# Pg5-Power_supply_2.net
KiCad netlist of a schematic drawn in Altium Designer
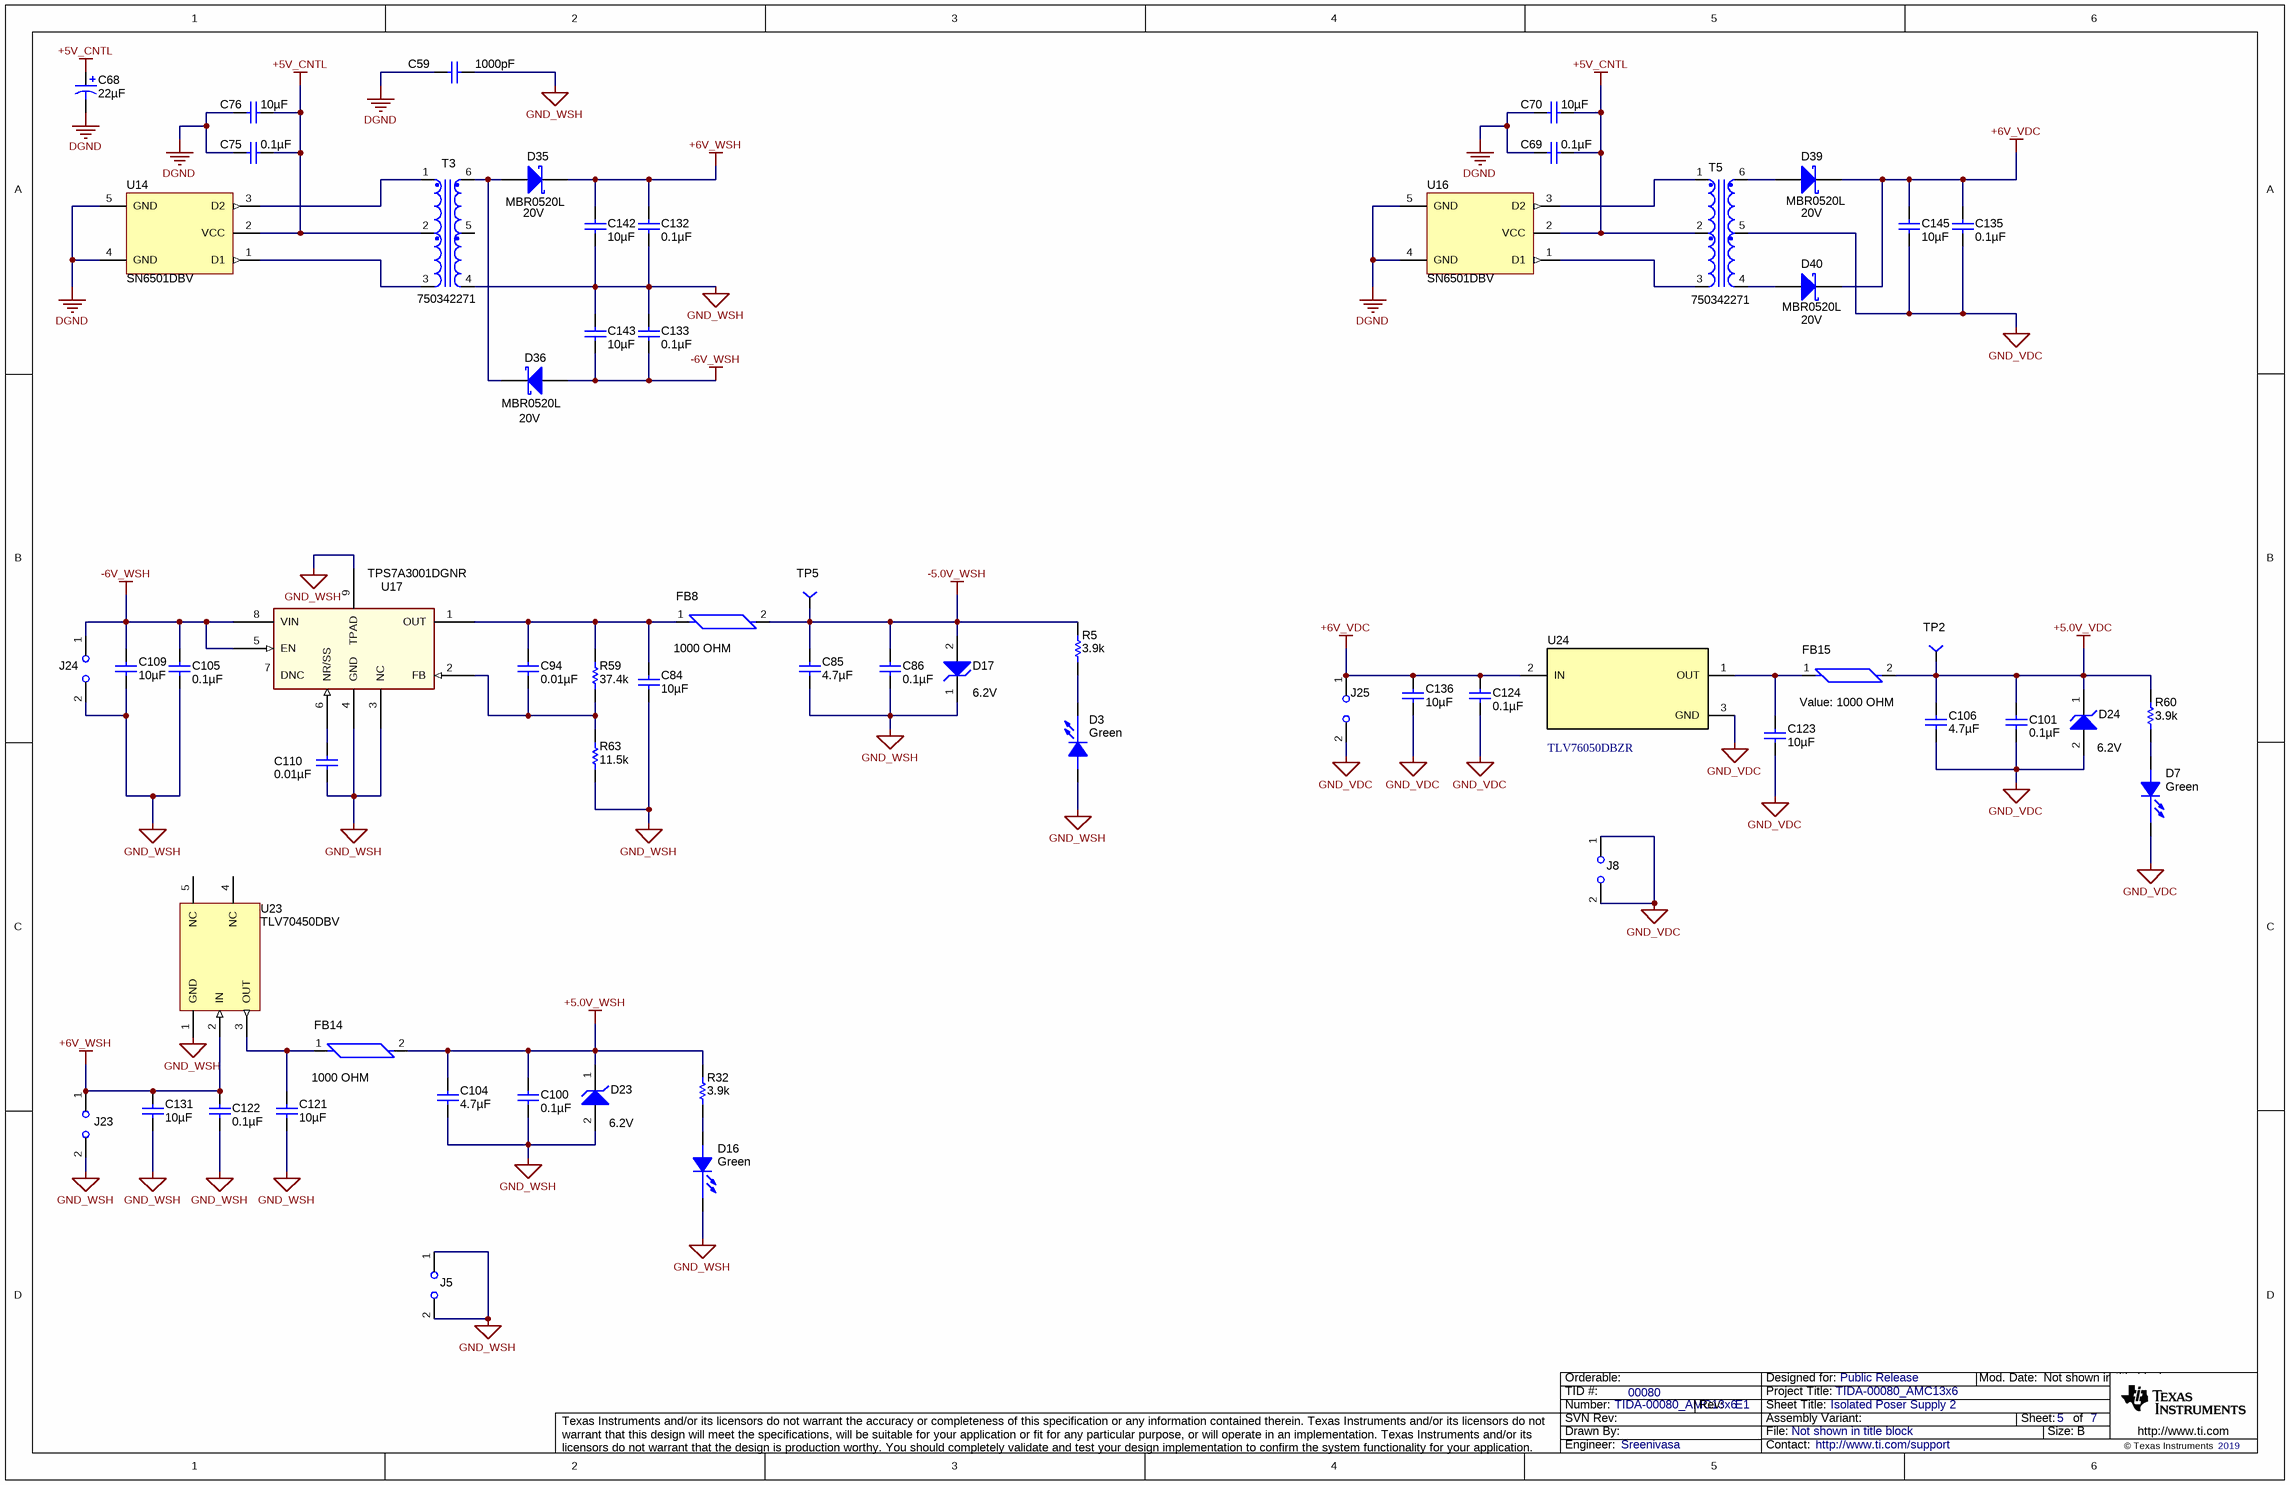
[diagram p0: Pg5-Power supply 2.SchDoc]

(export (version "E")
  (design (tool "Eeschema 10.0.6"))
  (components
    (comp (ref "C59")
      (value "1000pF")
      (footprint "CAP_200mil")
      (description "CAP CER 1000PF 1KV 10% RADIAL")
      (fields
        (field (name "PARTNUMBER") "S102K29Y5PN63J5R")
        (field (name "MANUFACTURER") "Vishay BC Components")
        (field (name "PUBLISHER") "Texas Instruments")
      )
      (libsource (lib "TI-INDIA-ALTIUM") (part "202R18W102KV4E"))
    )
    (comp (ref "C68")
      (value "UUD1E220MCL1GS")
      (footprint "ISE_MCS_SDM_E1_20MAY:SM_RADIAL_5MM")
      (description "CAP, AL, 22uF, 25V, +/-20%, 0.76 ohm, SMD")
      (fields
        (field (name "VALUEDISPLAYED") "22µF")
        (field (name "MANUFACTURER") "Nichicon")
        (field (name "PUBLISHER") "Texas Instruments")
      )
      (libsource (lib "Capacitor_Aluminum") (part "UUD1E220MCL1GS"))
    )
    (comp (ref "C69")
      (value "~")
      (footprint "ISE_MCS_SDM_E1_20MAY:0603")
      (description "CAP, CERM, 0.1uF, 50V, +/-10%, X7R, 0603")
      (fields
        (field (name "PARTNUMBER") "C0603C104K5RACTU")
        (field (name "VALUEDISPLAYED") "0.1µF")
        (field (name "MANUFACTURER") "Kemet")
        (field (name "PUBLISHER") "Texas Instruments")
      )
      (libsource (lib "Capacitor_Ceramic") (part "C0603C104K5RACTU"))
    )
    (comp (ref "C70")
      (value "~")
      (footprint "ISE_MCS_SDM_E1_20MAY:1210")
      (description "CAP, CERM, 10uF, 35V, +/-20%, X7R, 1210")
      (fields
        (field (name "PARTNUMBER") "GMK325AB7106MM-T")
        (field (name "VALUEDISPLAYED") "10µF")
        (field (name "MANUFACTURER") "Taiyo Yuden")
        (field (name "PUBLISHER") "Texas Instruments")
      )
      (libsource (lib "Capacitor_Ceramic") (part "GMK325AB7106MM-T"))
    )
    (comp (ref "C75")
      (value "~")
      (footprint "ISE_MCS_SDM_E1_20MAY:0603")
      (description "CAP, CERM, 0.1uF, 50V, +/-10%, X7R, 0603")
      (fields
        (field (name "PARTNUMBER") "C0603C104K5RACTU")
        (field (name "VALUEDISPLAYED") "0.1µF")
        (field (name "MANUFACTURER") "Kemet")
        (field (name "PUBLISHER") "Texas Instruments")
      )
      (libsource (lib "Capacitor_Ceramic") (part "C0603C104K5RACTU"))
    )
    (comp (ref "C76")
      (value "~")
      (footprint "ISE_MCS_SDM_E1_20MAY:1210")
      (description "CAP, CERM, 10uF, 35V, +/-20%, X7R, 1210")
      (fields
        (field (name "PARTNUMBER") "GMK325AB7106MM-T")
        (field (name "VALUEDISPLAYED") "10µF")
        (field (name "MANUFACTURER") "Taiyo Yuden")
        (field (name "PUBLISHER") "Texas Instruments")
      )
      (libsource (lib "Capacitor_Ceramic") (part "GMK325AB7106MM-T"))
    )
    (comp (ref "C84")
      (value "~")
      (footprint "ISE_MCS_SDM_E1_20MAY:1210")
      (description "CAP, CERM, 10uF, 35V, +/-20%, X7R, 1210")
      (fields
        (field (name "PARTNUMBER") "GMK325AB7106MM-T")
        (field (name "VALUEDISPLAYED") "10µF")
        (field (name "MANUFACTURER") "Taiyo Yuden")
        (field (name "PUBLISHER") "Texas Instruments")
      )
      (libsource (lib "Capacitor_Ceramic") (part "GMK325AB7106MM-T"))
    )
    (comp (ref "C85")
      (value "~")
      (footprint "ISE_MCS_SDM_E1_20MAY:0805_HV")
      (description "CAP, CERM, 4.7uF, 50V, +/-10%, X5R, 0805")
      (fields
        (field (name "PARTNUMBER") "C2012X5R1H475K125AB")
        (field (name "VALUEDISPLAYED") "4.7µF")
        (field (name "MANUFACTURER") "TDK")
        (field (name "PUBLISHER") "Texas Instruments")
      )
      (libsource (lib "Capacitor_Ceramic") (part "C2012X5R1H475K125AB"))
    )
    (comp (ref "C86")
      (value "~")
      (footprint "ISE_MCS_SDM_E1_20MAY:0603")
      (description "CAP, CERM, 0.1uF, 50V, +/-10%, X7R, 0603")
      (fields
        (field (name "PARTNUMBER") "C0603C104K5RACTU")
        (field (name "VALUEDISPLAYED") "0.1µF")
        (field (name "MANUFACTURER") "Kemet")
        (field (name "PUBLISHER") "Texas Instruments")
      )
      (libsource (lib "Capacitor_Ceramic") (part "C0603C104K5RACTU"))
    )
    (comp (ref "C94")
      (value "~")
      (footprint "ISE_MCS_SDM_E1_20MAY:0603")
      (description "CAP, CERM, 0.01uF, 100V, +/-5%, X7R, 0603")
      (fields
        (field (name "PARTNUMBER") "06031C103J4Z4A")
        (field (name "VALUEDISPLAYED") "0.01µF")
        (field (name "MANUFACTURER") "AVX")
        (field (name "PUBLISHER") "Texas Instruments")
      )
      (libsource (lib "Capacitor_Ceramic") (part "06031C103J4Z4A"))
    )
    (comp (ref "C100")
      (value "~")
      (footprint "ISE_MCS_SDM_E1_20MAY:0603")
      (description "CAP, CERM, 0.1uF, 50V, +/-10%, X7R, 0603")
      (fields
        (field (name "PARTNUMBER") "C0603C104K5RACTU")
        (field (name "VALUEDISPLAYED") "0.1µF")
        (field (name "MANUFACTURER") "Kemet")
        (field (name "PUBLISHER") "Texas Instruments")
      )
      (libsource (lib "Capacitor_Ceramic") (part "C0603C104K5RACTU"))
    )
    (comp (ref "C101")
      (value "~")
      (footprint "ISE_MCS_SDM_E1_20MAY:0603")
      (description "CAP, CERM, 0.1uF, 50V, +/-10%, X7R, 0603")
      (fields
        (field (name "PARTNUMBER") "C0603C104K5RACTU")
        (field (name "VALUEDISPLAYED") "0.1µF")
        (field (name "MANUFACTURER") "Kemet")
        (field (name "PUBLISHER") "Texas Instruments")
      )
      (libsource (lib "Capacitor_Ceramic") (part "C0603C104K5RACTU"))
    )
    (comp (ref "C104")
      (value "~")
      (footprint "ISE_MCS_SDM_E1_20MAY:0805_HV")
      (description "CAP, CERM, 4.7uF, 50V, +/-10%, X5R, 0805")
      (fields
        (field (name "PARTNUMBER") "C2012X5R1H475K125AB")
        (field (name "VALUEDISPLAYED") "4.7µF")
        (field (name "MANUFACTURER") "TDK")
        (field (name "PUBLISHER") "Texas Instruments")
      )
      (libsource (lib "Capacitor_Ceramic") (part "C2012X5R1H475K125AB"))
    )
    (comp (ref "C105")
      (value "~")
      (footprint "ISE_MCS_SDM_E1_20MAY:0603")
      (description "CAP, CERM, 0.1uF, 50V, +/-10%, X7R, 0603")
      (fields
        (field (name "PARTNUMBER") "C0603C104K5RACTU")
        (field (name "VALUEDISPLAYED") "0.1µF")
        (field (name "MANUFACTURER") "Kemet")
        (field (name "PUBLISHER") "Texas Instruments")
      )
      (libsource (lib "Capacitor_Ceramic") (part "C0603C104K5RACTU"))
    )
    (comp (ref "C106")
      (value "~")
      (footprint "ISE_MCS_SDM_E1_20MAY:0805_HV")
      (description "CAP, CERM, 4.7uF, 50V, +/-10%, X5R, 0805")
      (fields
        (field (name "PARTNUMBER") "C2012X5R1H475K125AB")
        (field (name "VALUEDISPLAYED") "4.7µF")
        (field (name "MANUFACTURER") "TDK")
        (field (name "PUBLISHER") "Texas Instruments")
      )
      (libsource (lib "Capacitor_Ceramic") (part "C2012X5R1H475K125AB"))
    )
    (comp (ref "C109")
      (value "~")
      (footprint "ISE_MCS_SDM_E1_20MAY:1210")
      (description "CAP, CERM, 10uF, 35V, +/-20%, X7R, 1210")
      (fields
        (field (name "PARTNUMBER") "GMK325AB7106MM-T")
        (field (name "VALUEDISPLAYED") "10µF")
        (field (name "MANUFACTURER") "Taiyo Yuden")
        (field (name "PUBLISHER") "Texas Instruments")
      )
      (libsource (lib "Capacitor_Ceramic") (part "GMK325AB7106MM-T"))
    )
    (comp (ref "C110")
      (value "~")
      (footprint "ISE_MCS_SDM_E1_20MAY:0603")
      (description "CAP, CERM, 0.01uF, 100V, +/-5%, X7R, 0603")
      (fields
        (field (name "PARTNUMBER") "06031C103J4Z4A")
        (field (name "VALUEDISPLAYED") "0.01µF")
        (field (name "MANUFACTURER") "AVX")
        (field (name "PUBLISHER") "Texas Instruments")
      )
      (libsource (lib "Capacitor_Ceramic") (part "06031C103J4Z4A"))
    )
    (comp (ref "C121")
      (value "~")
      (footprint "ISE_MCS_SDM_E1_20MAY:1210")
      (description "CAP, CERM, 10uF, 35V, +/-20%, X7R, 1210")
      (fields
        (field (name "PARTNUMBER") "GMK325AB7106MM-T")
        (field (name "VALUEDISPLAYED") "10µF")
        (field (name "MANUFACTURER") "Taiyo Yuden")
        (field (name "PUBLISHER") "Texas Instruments")
      )
      (libsource (lib "Capacitor_Ceramic") (part "GMK325AB7106MM-T"))
    )
    (comp (ref "C122")
      (value "~")
      (footprint "ISE_MCS_SDM_E1_20MAY:0603")
      (description "CAP, CERM, 0.1uF, 50V, +/-10%, X7R, 0603")
      (fields
        (field (name "PARTNUMBER") "C0603C104K5RACTU")
        (field (name "VALUEDISPLAYED") "0.1µF")
        (field (name "MANUFACTURER") "Kemet")
        (field (name "PUBLISHER") "Texas Instruments")
      )
      (libsource (lib "Capacitor_Ceramic") (part "C0603C104K5RACTU"))
    )
    (comp (ref "C123")
      (value "~")
      (footprint "ISE_MCS_SDM_E1_20MAY:1210")
      (description "CAP, CERM, 10uF, 35V, +/-20%, X7R, 1210")
      (fields
        (field (name "PARTNUMBER") "GMK325AB7106MM-T")
        (field (name "VALUEDISPLAYED") "10µF")
        (field (name "MANUFACTURER") "Taiyo Yuden")
        (field (name "PUBLISHER") "Texas Instruments")
      )
      (libsource (lib "Capacitor_Ceramic") (part "GMK325AB7106MM-T"))
    )
    (comp (ref "C124")
      (value "~")
      (footprint "ISE_MCS_SDM_E1_20MAY:0603")
      (description "CAP, CERM, 0.1uF, 50V, +/-10%, X7R, 0603")
      (fields
        (field (name "PARTNUMBER") "C0603C104K5RACTU")
        (field (name "VALUEDISPLAYED") "0.1µF")
        (field (name "MANUFACTURER") "Kemet")
        (field (name "PUBLISHER") "Texas Instruments")
      )
      (libsource (lib "Capacitor_Ceramic") (part "C0603C104K5RACTU"))
    )
    (comp (ref "C131")
      (value "~")
      (footprint "ISE_MCS_SDM_E1_20MAY:1210")
      (description "CAP, CERM, 10uF, 35V, +/-20%, X7R, 1210")
      (fields
        (field (name "PARTNUMBER") "GMK325AB7106MM-T")
        (field (name "VALUEDISPLAYED") "10µF")
        (field (name "MANUFACTURER") "Taiyo Yuden")
        (field (name "PUBLISHER") "Texas Instruments")
      )
      (libsource (lib "Capacitor_Ceramic") (part "GMK325AB7106MM-T"))
    )
    (comp (ref "C132")
      (value "~")
      (footprint "ISE_MCS_SDM_E1_20MAY:0603")
      (description "CAP, CERM, 0.1uF, 50V, +/-10%, X7R, 0603")
      (fields
        (field (name "PARTNUMBER") "C0603C104K5RACTU")
        (field (name "VALUEDISPLAYED") "0.1µF")
        (field (name "MANUFACTURER") "Kemet")
        (field (name "PUBLISHER") "Texas Instruments")
      )
      (libsource (lib "Capacitor_Ceramic") (part "C0603C104K5RACTU"))
    )
    (comp (ref "C133")
      (value "~")
      (footprint "ISE_MCS_SDM_E1_20MAY:0603")
      (description "CAP, CERM, 0.1uF, 50V, +/-10%, X7R, 0603")
      (fields
        (field (name "PARTNUMBER") "C0603C104K5RACTU")
        (field (name "VALUEDISPLAYED") "0.1µF")
        (field (name "MANUFACTURER") "Kemet")
        (field (name "PUBLISHER") "Texas Instruments")
      )
      (libsource (lib "Capacitor_Ceramic") (part "C0603C104K5RACTU"))
    )
    (comp (ref "C135")
      (value "~")
      (footprint "ISE_MCS_SDM_E1_20MAY:0603")
      (description "CAP, CERM, 0.1uF, 50V, +/-10%, X7R, 0603")
      (fields
        (field (name "PARTNUMBER") "C0603C104K5RACTU")
        (field (name "VALUEDISPLAYED") "0.1µF")
        (field (name "MANUFACTURER") "Kemet")
        (field (name "PUBLISHER") "Texas Instruments")
      )
      (libsource (lib "Capacitor_Ceramic") (part "C0603C104K5RACTU"))
    )
    (comp (ref "C136")
      (value "~")
      (footprint "ISE_MCS_SDM_E1_20MAY:1210")
      (description "CAP, CERM, 10uF, 35V, +/-20%, X7R, 1210")
      (fields
        (field (name "PARTNUMBER") "GMK325AB7106MM-T")
        (field (name "VALUEDISPLAYED") "10µF")
        (field (name "MANUFACTURER") "Taiyo Yuden")
        (field (name "PUBLISHER") "Texas Instruments")
      )
      (libsource (lib "Capacitor_Ceramic") (part "GMK325AB7106MM-T"))
    )
    (comp (ref "C142")
      (value "~")
      (footprint "ISE_MCS_SDM_E1_20MAY:1210")
      (description "CAP, CERM, 10uF, 35V, +/-20%, X7R, 1210")
      (fields
        (field (name "PARTNUMBER") "GMK325AB7106MM-T")
        (field (name "VALUEDISPLAYED") "10µF")
        (field (name "MANUFACTURER") "Taiyo Yuden")
        (field (name "PUBLISHER") "Texas Instruments")
      )
      (libsource (lib "Capacitor_Ceramic") (part "GMK325AB7106MM-T"))
    )
    (comp (ref "C143")
      (value "~")
      (footprint "ISE_MCS_SDM_E1_20MAY:1210")
      (description "CAP, CERM, 10uF, 35V, +/-20%, X7R, 1210")
      (fields
        (field (name "PARTNUMBER") "GMK325AB7106MM-T")
        (field (name "VALUEDISPLAYED") "10µF")
        (field (name "MANUFACTURER") "Taiyo Yuden")
        (field (name "PUBLISHER") "Texas Instruments")
      )
      (libsource (lib "Capacitor_Ceramic") (part "GMK325AB7106MM-T"))
    )
    (comp (ref "C145")
      (value "~")
      (footprint "ISE_MCS_SDM_E1_20MAY:1210")
      (description "CAP, CERM, 10uF, 35V, +/-20%, X7R, 1210")
      (fields
        (field (name "PARTNUMBER") "GMK325AB7106MM-T")
        (field (name "VALUEDISPLAYED") "10µF")
        (field (name "MANUFACTURER") "Taiyo Yuden")
        (field (name "PUBLISHER") "Texas Instruments")
      )
      (libsource (lib "Capacitor_Ceramic") (part "GMK325AB7106MM-T"))
    )
    (comp (ref "D3")
      (value "Green")
      (footprint "ISE_MCS_SDM_E1_20MAY:LED0603AA")
      (description "LED SmartLED Green 570NM")
      (fields
        (field (name "PARTNUMBER") "LG L29K-G2J1-24-Z")
        (field (name "MANUFACTURER") "OSRAM")
        (field (name "PUBLISHER") "TI")
        (field (name "SYMBOLCREATOR") "x0120606")
      )
      (libsource (lib "TI-INDIA-ALTIUM") (part "LED_LG L29K-G2J1-24-Z"))
    )
    (comp (ref "D7")
      (value "Green")
      (footprint "ISE_MCS_SDM_E1_20MAY:LED0603AA")
      (description "LED SmartLED Green 570NM")
      (fields
        (field (name "PARTNUMBER") "LG L29K-G2J1-24-Z")
        (field (name "MANUFACTURER") "OSRAM")
        (field (name "PUBLISHER") "TI")
        (field (name "SYMBOLCREATOR") "x0120606")
      )
      (libsource (lib "TI-INDIA-ALTIUM") (part "LED_LG L29K-G2J1-24-Z"))
    )
    (comp (ref "D16")
      (value "Green")
      (footprint "ISE_MCS_SDM_E1_20MAY:LED0603AA")
      (description "LED SmartLED Green 570NM")
      (fields
        (field (name "PARTNUMBER") "LG L29K-G2J1-24-Z")
        (field (name "MANUFACTURER") "OSRAM")
        (field (name "PUBLISHER") "TI")
        (field (name "SYMBOLCREATOR") "x0120606")
      )
      (libsource (lib "TI-INDIA-ALTIUM") (part "LED_LG L29K-G2J1-24-Z"))
    )
    (comp (ref "D17")
      (value "6.2V")
      (footprint "ISE_MCS_SDM_E1_20MAY:powerDI123")
      (description "Diode, Zener, 6.2V, 1W, PowerDI123")
      (fields
        (field (name "PARTNUMBER") "DFLZ6V2-7")
        (field (name "MANUFACTURER") "Diodes Inc.")
        (field (name "PUBLISHER") "Texas Instruments")
      )
      (libsource (lib "ZenerDiodes") (part "DFLZ6V2-7"))
    )
    (comp (ref "D23")
      (value "6.2V")
      (footprint "ISE_MCS_SDM_E1_20MAY:powerDI123")
      (description "Diode, Zener, 6.2V, 1W, PowerDI123")
      (fields
        (field (name "PARTNUMBER") "DFLZ6V2-7")
        (field (name "MANUFACTURER") "Diodes Inc.")
        (field (name "PUBLISHER") "Texas Instruments")
      )
      (libsource (lib "ZenerDiodes") (part "DFLZ6V2-7"))
    )
    (comp (ref "D24")
      (value "6.2V")
      (footprint "ISE_MCS_SDM_E1_20MAY:powerDI123")
      (description "Diode, Zener, 6.2V, 1W, PowerDI123")
      (fields
        (field (name "PARTNUMBER") "DFLZ6V2-7")
        (field (name "MANUFACTURER") "Diodes Inc.")
        (field (name "PUBLISHER") "Texas Instruments")
      )
      (libsource (lib "ZenerDiodes") (part "DFLZ6V2-7"))
    )
    (comp (ref "D35")
      (value "MBR0520L")
      (footprint "ISE_MCS_SDM_E1_20MAY:SOD-123")
      (description "Diode, Schottky, 20V, 0.5A, SOD-123")
      (fields
        (field (name "ALTIUM_VALUE") "20V")
        (field (name "MANUFACTURER") "Fairchild Semiconductor")
        (field (name "PUBLISHER") "Texas Instruments")
      )
      (libsource (lib "Diode") (part "MBR0520LT1G"))
    )
    (comp (ref "D36")
      (value "MBR0520L")
      (footprint "ISE_MCS_SDM_E1_20MAY:SOD-123")
      (description "Diode, Schottky, 20V, 0.5A, SOD-123")
      (fields
        (field (name "ALTIUM_VALUE") "20V")
        (field (name "MANUFACTURER") "Fairchild Semiconductor")
        (field (name "PUBLISHER") "Texas Instruments")
      )
      (libsource (lib "Diode") (part "MBR0520LT1G"))
    )
    (comp (ref "D39")
      (value "MBR0520L")
      (footprint "ISE_MCS_SDM_E1_20MAY:SOD-123")
      (description "Diode, Schottky, 20V, 0.5A, SOD-123")
      (fields
        (field (name "ALTIUM_VALUE") "20V")
        (field (name "MANUFACTURER") "Fairchild Semiconductor")
        (field (name "PUBLISHER") "Texas Instruments")
      )
      (libsource (lib "Diode") (part "MBR0520LT1G"))
    )
    (comp (ref "D40")
      (value "MBR0520L")
      (footprint "ISE_MCS_SDM_E1_20MAY:SOD-123")
      (description "Diode, Schottky, 20V, 0.5A, SOD-123")
      (fields
        (field (name "ALTIUM_VALUE") "20V")
        (field (name "MANUFACTURER") "Fairchild Semiconductor")
        (field (name "PUBLISHER") "Texas Instruments")
      )
      (libsource (lib "Diode") (part "MBR0520LT1G"))
    )
    (comp (ref "FB8")
      (value "1000 OHM")
      (footprint "ISE_MCS_SDM_E1_20MAY:FB0603")
      (description "FERRITE CHIP 1000 OHM 300MA 0603")
      (fields
        (field (name "PARTNUMBER") "MMZ1608B102C")
        (field (name "MANUFACTURER") "TDK Corporation")
        (field (name "PUBLISHER") "TI")
      )
      (libsource (lib "TI-INDIA-ALTIUM") (part "MMZ1608B102C"))
    )
    (comp (ref "FB14")
      (value "1000 OHM")
      (footprint "ISE_MCS_SDM_E1_20MAY:FB0603")
      (description "FERRITE CHIP 1000 OHM 300MA 0603")
      (fields
        (field (name "PARTNUMBER") "MMZ1608B102C")
        (field (name "MANUFACTURER") "TDK Corporation")
        (field (name "PUBLISHER") "TI")
      )
      (libsource (lib "TI-INDIA-ALTIUM") (part "MMZ1608B102C"))
    )
    (comp (ref "FB15")
      (value "1000 OHM")
      (footprint "ISE_MCS_SDM_E1_20MAY:FB0603")
      (description "FERRITE CHIP 1000 OHM 300MA 0603")
      (fields
        (field (name "PARTNUMBER") "MMZ1608B102C")
        (field (name "MANUFACTURER") "TDK Corporation")
        (field (name "PUBLISHER") "TI")
      )
      (libsource (lib "TI-INDIA-ALTIUM") (part "MMZ1608B102C"))
    )
    (comp (ref "J5")
      (value "~")
      (footprint "ISE_MCS_SDM_E1_20MAY:HDR100_1X2")
      (description "Header, Male 2-pin, 100mil spacing,")
      (fields (field (name "MANUFACTURER") "FCI") (field (name "PARTNUMBER") "68001-402HLF"))
      (libsource (lib "PADSlegacy_Hardware") (part "JUMPER_2X100MIL"))
    )
    (comp (ref "J8")
      (value "~")
      (footprint "ISE_MCS_SDM_E1_20MAY:HDR100_1X2")
      (description "Header, Male 2-pin, 100mil spacing,")
      (fields (field (name "MANUFACTURER") "FCI") (field (name "PARTNUMBER") "68001-402HLF"))
      (libsource (lib "PADSlegacy_Hardware") (part "JUMPER_2X100MIL"))
    )
    (comp (ref "J23")
      (value "~")
      (footprint "ISE_MCS_SDM_E1_20MAY:HDR100_1X2")
      (description "Header, Male 2-pin, 100mil spacing,")
      (fields (field (name "MANUFACTURER") "FCI") (field (name "PARTNUMBER") "68001-402HLF"))
      (libsource (lib "PADSlegacy_Hardware") (part "JUMPER_2X100MIL"))
    )
    (comp (ref "J24")
      (value "~")
      (footprint "ISE_MCS_SDM_E1_20MAY:HDR100_1X2")
      (description "Header, Male 2-pin, 100mil spacing,")
      (fields (field (name "MANUFACTURER") "FCI") (field (name "PARTNUMBER") "68001-402HLF"))
      (libsource (lib "PADSlegacy_Hardware") (part "JUMPER_2X100MIL"))
    )
    (comp (ref "J25")
      (value "~")
      (footprint "ISE_MCS_SDM_E1_20MAY:HDR100_1X2")
      (description "Header, Male 2-pin, 100mil spacing,")
      (fields (field (name "MANUFACTURER") "FCI") (field (name "PARTNUMBER") "68001-402HLF"))
      (libsource (lib "PADSlegacy_Hardware") (part "JUMPER_2X100MIL"))
    )
    (comp (ref "R5")
      (value "3.9k")
      (footprint "ISE_MCS_SDM_E1_20MAY:0603")
      (description "RES, 3.9k ohm, 5%, 0.1W, 0603")
      (fields
        (field (name "PARTNUMBER") "CRCW06033K90JNEA")
        (field (name "MANUFACTURER") "Vishay-Dale")
        (field (name "PUBLISHER") "Texas Instruments")
      )
      (libsource (lib "Resistor_0603") (part "CRCW06033K90JNEA"))
    )
    (comp (ref "R32")
      (value "3.9k")
      (footprint "ISE_MCS_SDM_E1_20MAY:0603")
      (description "RES, 3.9k ohm, 5%, 0.1W, 0603")
      (fields
        (field (name "PARTNUMBER") "CRCW06033K90JNEA")
        (field (name "MANUFACTURER") "Vishay-Dale")
        (field (name "PUBLISHER") "Texas Instruments")
      )
      (libsource (lib "Resistor_0603") (part "CRCW06033K90JNEA"))
    )
    (comp (ref "R59")
      (value "37.4k")
      (footprint "ISE_MCS_SDM_E1_20MAY:0603")
      (description "RES 37.4K OHM 1/10W .1% 0603 SMD")
      (fields
        (field (name "PARTNUMBER") "ERA-3AEB3742V")
        (field (name "MANUFACTURER") "Panasonic")
        (field (name "PUBLISHER") "Texas Instruments")
      )
      (libsource (lib "Resistor_0603") (part "RT0603BRD0737KL"))
    )
    (comp (ref "R60")
      (value "3.9k")
      (footprint "ISE_MCS_SDM_E1_20MAY:0603")
      (description "RES, 3.9k ohm, 5%, 0.1W, 0603")
      (fields
        (field (name "PARTNUMBER") "CRCW06033K90JNEA")
        (field (name "MANUFACTURER") "Vishay-Dale")
        (field (name "PUBLISHER") "Texas Instruments")
      )
      (libsource (lib "Resistor_0603") (part "CRCW06033K90JNEA"))
    )
    (comp (ref "R63")
      (value "11.5k")
      (footprint "ISE_MCS_SDM_E1_20MAY:0603")
      (description "RES, 11.5k ohm, 1%, 0.1W, 0603")
      (fields
        (field (name "PARTNUMBER") "CRCW060311K5FKEA")
        (field (name "MANUFACTURER") "Vishay-Dale")
        (field (name "PUBLISHER") "Texas Instruments")
      )
      (libsource (lib "Resistor_0603") (part "CRCW060311K5FKEA"))
    )
    (comp (ref "T3")
      (value "750342271")
      (footprint "760390015")
      (description "Transformer 469uH SMD")
      (fields (field (name "MANUFACTURER") "Wurth Electronics Midcom") (field (name "PUBLISHER") "TI"))
      (libsource (lib "Isolated current sensing") (part "TRNSFMR"))
    )
    (comp (ref "T5")
      (value "750342271")
      (footprint "760390015")
      (description "Transformer 469uH SMD")
      (fields (field (name "MANUFACTURER") "Wurth Electronics Midcom") (field (name "PUBLISHER") "TI"))
      (libsource (lib "Isolated current sensing") (part "TRNSFMR"))
    )
    (comp (ref "TP2")
      (value "~")
      (footprint "ISE_MCS_SDM_E1_20MAY:TP-040_RND")
      (description "Test Point, O.040 Hole")
      (fields (field (name "MANUFACTURER") "STD"))
      (libsource (lib "PADSlegacy_Hardware") (part "TP-040_RND"))
    )
    (comp (ref "TP5")
      (value "~")
      (footprint "ISE_MCS_SDM_E1_20MAY:TP-040_RND")
      (description "Test Point, O.040 Hole")
      (fields (field (name "MANUFACTURER") "STD"))
      (libsource (lib "PADSlegacy_Hardware") (part "TP-040_RND"))
    )
    (comp (ref "U14")
      (value "SN6501DBV")
      (footprint "ISE_MCS_SDM_E1_20MAY:DBV0005A_N")
      (description "Transformer Driver for Isolated Power Supplies, DBV0005A")
      (fields
        (field (name "MANUFACTURER") "Texas Instruments")
        (field (name "SYMBOLCREATOR") "a0411947")
        (field (name "PUBLISHER") "Texas Instruments")
      )
      (libsource (lib "TI_Pre_Release") (part "SN6501DBV"))
    )
    (comp (ref "U16")
      (value "SN6501DBV")
      (footprint "ISE_MCS_SDM_E1_20MAY:DBV0005A_N")
      (description "Transformer Driver for Isolated Power Supplies, DBV0005A")
      (fields
        (field (name "MANUFACTURER") "Texas Instruments")
        (field (name "SYMBOLCREATOR") "a0411947")
        (field (name "PUBLISHER") "Texas Instruments")
      )
      (libsource (lib "TI_Pre_Release") (part "SN6501DBV"))
    )
    (comp (ref "U17")
      (value "~")
      (footprint "ISE_MCS_SDM_E1_20MAY:MSOP8(DGN)")
      (description "-36V, -200mA, Ultralow-Noise, Negative Linear Regulator")
      (fields
        (field (name "MANUFACTURER") "Texas Instruments")
        (field (name "PARTNUMBER") "TPS7A3001DGNR")
        (field (name "PUBLISHER") "Texas Instruments")
        (field (name "SYMBOLCREATOR") "x0120606")
      )
      (libsource (lib "TI-INDIA-ALTIUM") (part "TPS7A3001DGNR"))
    )
    (comp (ref "U23")
      (value "TLV70450DBV")
      (footprint "ISE_MCS_SDM_E1_20MAY:DBV0005A_N")
      (description "Regulator, LDO, 5V, 0.15A, SOT23-5")
      (fields
        (field (name "MANUFACTURER") "Texas Instruments")
        (field (name "SYMBOLCREATOR") "x0120606")
        (field (name "PUBLISHER") "Texas Instruments")
      )
      (libsource (lib "TI-INDIA-ALTIUM") (part "TLV70450DBV"))
    )
    (comp (ref "U24")
      (value "TLV76050DBZR")
      (footprint "DBZ0003A_N")
      (description "100-mA, 30-V, Fixed-Output, Linear-Voltage Regulator, DBZ0003A (SOT-23-3)")
      (fields
        (field (name "ALTERNATE PARTNUMBER") "TLV76050DBZT")
        (field (name "MANUFACTURER") "Texas Instruments")
        (field (name "PARTNUMBER") "TLV76050DBZR")
      )
      (libsource (lib "Altium Vault - TI") (part "TLV760xx"))
    )
  )
  (nets
    (net (code "1") (name "+5.0V_VDC") (class "Default")
      (node (ref "C101") (pin "1") (pinfunction "1_1") (pintype "passive"))
      (node (ref "C106") (pin "2") (pinfunction "2_2") (pintype "passive"))
      (node (ref "D24") (pin "1") (pinfunction "K_1") (pintype "passive"))
      (node (ref "FB15") (pin "2") (pinfunction "2_2") (pintype "passive"))
      (node (ref "R60") (pin "2") (pinfunction "2_2") (pintype "passive"))
      (node (ref "TP2") (pin "1") (pinfunction "1_1") (pintype "passive"))
    )
    (net (code "2") (name "+5.0V_WSH") (class "Default")
      (node (ref "C100") (pin "1") (pinfunction "1_1") (pintype "passive"))
      (node (ref "C104") (pin "2") (pinfunction "2_2") (pintype "passive"))
      (node (ref "D23") (pin "1") (pinfunction "K_1") (pintype "passive"))
      (node (ref "FB14") (pin "2") (pinfunction "2_2") (pintype "passive"))
      (node (ref "R32") (pin "2") (pinfunction "2_2") (pintype "passive"))
    )
    (net (code "3") (name "+5V_CNTL") (class "Default")
      (node (ref "C68") (pin "1") (pinfunction "+_1") (pintype "passive"))
      (node (ref "C69") (pin "2") (pinfunction "2_2") (pintype "passive"))
      (node (ref "C70") (pin "2") (pinfunction "2_2") (pintype "passive"))
      (node (ref "C75") (pin "2") (pinfunction "2_2") (pintype "passive"))
      (node (ref "C76") (pin "2") (pinfunction "2_2") (pintype "passive"))
      (node (ref "T3") (pin "2") (pinfunction "2_2") (pintype "passive"))
      (node (ref "T5") (pin "2") (pinfunction "2_2") (pintype "passive"))
      (node (ref "U14") (pin "2") (pinfunction "VCC_2") (pintype "power_in"))
      (node (ref "U16") (pin "2") (pinfunction "VCC_2") (pintype "power_in"))
    )
    (net (code "4") (name "+6V_VDC") (class "Default")
      (node (ref "C124") (pin "1") (pinfunction "1_1") (pintype "passive"))
      (node (ref "C135") (pin "1") (pinfunction "1_1") (pintype "passive"))
      (node (ref "C136") (pin "2") (pinfunction "2_2") (pintype "passive"))
      (node (ref "C145") (pin "1") (pinfunction "1_1") (pintype "passive"))
      (node (ref "D39") (pin "1") (pinfunction "K_1") (pintype "passive"))
      (node (ref "D40") (pin "1") (pinfunction "K_1") (pintype "passive"))
      (node (ref "J25") (pin "1") (pintype "passive"))
      (node (ref "U24") (pin "2") (pinfunction "IN_2") (pintype "power_in"))
    )
    (net (code "5") (name "+6V_WSH") (class "Default")
      (node (ref "C122") (pin "1") (pinfunction "1_1") (pintype "passive"))
      (node (ref "C131") (pin "2") (pinfunction "2_2") (pintype "passive"))
      (node (ref "C132") (pin "1") (pinfunction "1_1") (pintype "passive"))
      (node (ref "C142") (pin "1") (pinfunction "1_1") (pintype "passive"))
      (node (ref "D35") (pin "1") (pinfunction "K_1") (pintype "passive"))
      (node (ref "J23") (pin "1") (pintype "passive"))
      (node (ref "U23") (pin "2") (pinfunction "IN_2") (pintype "input"))
    )
    (net (code "6") (name "-5.0V_WSH") (class "Default")
      (node (ref "C85") (pin "2") (pinfunction "2_2") (pintype "passive"))
      (node (ref "C86") (pin "1") (pinfunction "1_1") (pintype "passive"))
      (node (ref "D17") (pin "2") (pinfunction "A_2") (pintype "passive"))
      (node (ref "FB8") (pin "2") (pinfunction "2_2") (pintype "passive"))
      (node (ref "R5") (pin "2") (pinfunction "2_2") (pintype "passive"))
      (node (ref "TP5") (pin "1") (pinfunction "1_1") (pintype "passive"))
    )
    (net (code "7") (name "-6V_WSH") (class "Default")
      (node (ref "C105") (pin "1") (pinfunction "1_1") (pintype "passive"))
      (node (ref "C109") (pin "2") (pinfunction "2_2") (pintype "passive"))
      (node (ref "C133") (pin "2") (pinfunction "2_2") (pintype "passive"))
      (node (ref "C143") (pin "2") (pinfunction "2_2") (pintype "passive"))
      (node (ref "D36") (pin "2") (pinfunction "A_2") (pintype "passive"))
      (node (ref "J24") (pin "1") (pintype "passive"))
      (node (ref "U17") (pin "5") (pinfunction "EN_5") (pintype "input"))
      (node (ref "U17") (pin "8") (pinfunction "VIN_8") (pintype "power_in"))
    )
    (net (code "8") (name "DGND") (class "Default")
      (node (ref "C59") (pin "1") (pinfunction "1_1") (pintype "passive"))
      (node (ref "C68") (pin "2") (pinfunction "-_2") (pintype "passive"))
      (node (ref "C69") (pin "1") (pinfunction "1_1") (pintype "passive"))
      (node (ref "C70") (pin "1") (pinfunction "1_1") (pintype "passive"))
      (node (ref "C75") (pin "1") (pinfunction "1_1") (pintype "passive"))
      (node (ref "C76") (pin "1") (pinfunction "1_1") (pintype "passive"))
      (node (ref "U14") (pin "4") (pinfunction "GND_4") (pintype "power_in"))
      (node (ref "U14") (pin "5") (pinfunction "GND_5") (pintype "power_in"))
      (node (ref "U16") (pin "4") (pinfunction "GND_4") (pintype "power_in"))
      (node (ref "U16") (pin "5") (pinfunction "GND_5") (pintype "power_in"))
    )
    (net (code "9") (name "GND_VDC") (class "Default")
      (node (ref "C101") (pin "2") (pinfunction "2_2") (pintype "passive"))
      (node (ref "C106") (pin "1") (pinfunction "1_1") (pintype "passive"))
      (node (ref "C123") (pin "1") (pinfunction "1_1") (pintype "passive"))
      (node (ref "C124") (pin "2") (pinfunction "2_2") (pintype "passive"))
      (node (ref "C135") (pin "2") (pinfunction "2_2") (pintype "passive"))
      (node (ref "C136") (pin "1") (pinfunction "1_1") (pintype "passive"))
      (node (ref "C145") (pin "2") (pinfunction "2_2") (pintype "passive"))
      (node (ref "D24") (pin "2") (pinfunction "A_2") (pintype "passive"))
      (node (ref "D7") (pin "1") (pinfunction "C_1") (pintype "passive"))
      (node (ref "J25") (pin "2") (pintype "passive"))
      (node (ref "J8") (pin "1") (pintype "passive"))
      (node (ref "J8") (pin "2") (pintype "passive"))
      (node (ref "T5") (pin "5") (pinfunction "5_5") (pintype "passive"))
      (node (ref "U24") (pin "3") (pinfunction "GND_3") (pintype "power_in"))
    )
    (net (code "10") (name "GND_WSH") (class "Default")
      (node (ref "C100") (pin "2") (pinfunction "2_2") (pintype "passive"))
      (node (ref "C104") (pin "1") (pinfunction "1_1") (pintype "passive"))
      (node (ref "C105") (pin "2") (pinfunction "2_2") (pintype "passive"))
      (node (ref "C109") (pin "1") (pinfunction "1_1") (pintype "passive"))
      (node (ref "C110") (pin "1") (pinfunction "1_1") (pintype "passive"))
      (node (ref "C121") (pin "1") (pinfunction "1_1") (pintype "passive"))
      (node (ref "C122") (pin "2") (pinfunction "2_2") (pintype "passive"))
      (node (ref "C131") (pin "1") (pinfunction "1_1") (pintype "passive"))
      (node (ref "C132") (pin "2") (pinfunction "2_2") (pintype "passive"))
      (node (ref "C133") (pin "1") (pinfunction "1_1") (pintype "passive"))
      (node (ref "C142") (pin "2") (pinfunction "2_2") (pintype "passive"))
      (node (ref "C143") (pin "1") (pinfunction "1_1") (pintype "passive"))
      (node (ref "C59") (pin "2") (pinfunction "2_2") (pintype "passive"))
      (node (ref "C84") (pin "1") (pinfunction "1_1") (pintype "passive"))
      (node (ref "C85") (pin "1") (pinfunction "1_1") (pintype "passive"))
      (node (ref "C86") (pin "2") (pinfunction "2_2") (pintype "passive"))
      (node (ref "D16") (pin "1") (pinfunction "C_1") (pintype "passive"))
      (node (ref "D17") (pin "1") (pinfunction "K_1") (pintype "passive"))
      (node (ref "D23") (pin "2") (pinfunction "A_2") (pintype "passive"))
      (node (ref "D3") (pin "2") (pinfunction "A_2") (pintype "passive"))
      (node (ref "J23") (pin "2") (pintype "passive"))
      (node (ref "J24") (pin "2") (pintype "passive"))
      (node (ref "J5") (pin "1") (pintype "passive"))
      (node (ref "J5") (pin "2") (pintype "passive"))
      (node (ref "R63") (pin "1") (pinfunction "1_1") (pintype "passive"))
      (node (ref "T3") (pin "4") (pinfunction "4_4") (pintype "passive"))
      (node (ref "U17") (pin "3") (pinfunction "NC_3") (pintype "passive"))
      (node (ref "U17") (pin "4") (pinfunction "GND_4") (pintype "power_in"))
      (node (ref "U17") (pin "9") (pinfunction "TPAD_9") (pintype "passive"))
      (node (ref "U23") (pin "1") (pinfunction "GND_1") (pintype "power_in"))
    )
    (net (code "11") (name "Net-(D3-C)") (class "Default")
      (node (ref "D3") (pin "1") (pinfunction "C_1") (pintype "passive"))
      (node (ref "R5") (pin "1") (pinfunction "1_1") (pintype "passive"))
    )
    (net (code "12") (name "Net-(D7-A)") (class "Default")
      (node (ref "D7") (pin "2") (pinfunction "A_2") (pintype "passive"))
      (node (ref "R60") (pin "1") (pinfunction "1_1") (pintype "passive"))
    )
    (net (code "13") (name "Net-(D16-A)") (class "Default")
      (node (ref "D16") (pin "2") (pinfunction "A_2") (pintype "passive"))
      (node (ref "R32") (pin "1") (pinfunction "1_1") (pintype "passive"))
    )
    (net (code "14") (name "Net-(D35-A)") (class "Default")
      (node (ref "D35") (pin "2") (pinfunction "A_2") (pintype "passive"))
      (node (ref "D36") (pin "1") (pinfunction "K_1") (pintype "passive"))
      (node (ref "T3") (pin "6") (pinfunction "6_6") (pintype "passive"))
    )
    (net (code "15") (name "Net-(D39-A)") (class "Default")
      (node (ref "D39") (pin "2") (pinfunction "A_2") (pintype "passive"))
      (node (ref "T5") (pin "6") (pinfunction "6_6") (pintype "passive"))
    )
    (net (code "16") (name "Net-(D40-A)") (class "Default")
      (node (ref "D40") (pin "2") (pinfunction "A_2") (pintype "passive"))
      (node (ref "T5") (pin "4") (pinfunction "4_4") (pintype "passive"))
    )
    (net (code "17") (name "Net-(U14-D1)") (class "Default")
      (node (ref "T3") (pin "3") (pinfunction "3_3") (pintype "passive"))
      (node (ref "U14") (pin "1") (pinfunction "D1_1") (pintype "output"))
    )
    (net (code "18") (name "Net-(U14-D2)") (class "Default")
      (node (ref "T3") (pin "1") (pinfunction "1_1") (pintype "passive"))
      (node (ref "U14") (pin "3") (pinfunction "D2_3") (pintype "output"))
    )
    (net (code "19") (name "Net-(U16-D1)") (class "Default")
      (node (ref "T5") (pin "3") (pinfunction "3_3") (pintype "passive"))
      (node (ref "U16") (pin "1") (pinfunction "D1_1") (pintype "output"))
    )
    (net (code "20") (name "Net-(U16-D2)") (class "Default")
      (node (ref "T5") (pin "1") (pinfunction "1_1") (pintype "passive"))
      (node (ref "U16") (pin "3") (pinfunction "D2_3") (pintype "output"))
    )
    (net (code "21") (name "Net-(U17-FB)") (class "Default")
      (node (ref "C94") (pin "1") (pinfunction "1_1") (pintype "passive"))
      (node (ref "R59") (pin "1") (pinfunction "1_1") (pintype "passive"))
      (node (ref "R63") (pin "2") (pinfunction "2_2") (pintype "passive"))
      (node (ref "U17") (pin "2") (pinfunction "FB_2") (pintype "input"))
    )
    (net (code "22") (name "Net-(U17-NR{slash}SS)") (class "Default")
      (node (ref "C110") (pin "2") (pinfunction "2_2") (pintype "passive"))
      (node (ref "U17") (pin "6") (pinfunction "NR/SS_6") (pintype "input"))
    )
    (net (code "23") (name "Net-(U17-OUT)") (class "Default")
      (node (ref "C84") (pin "2") (pinfunction "2_2") (pintype "passive"))
      (node (ref "C94") (pin "2") (pinfunction "2_2") (pintype "passive"))
      (node (ref "FB8") (pin "1") (pinfunction "1_1") (pintype "passive"))
      (node (ref "R59") (pin "2") (pinfunction "2_2") (pintype "passive"))
      (node (ref "U17") (pin "1") (pinfunction "OUT_1") (pintype "power_in"))
    )
    (net (code "24") (name "Net-(U23-OUT)") (class "Default")
      (node (ref "C121") (pin "2") (pinfunction "2_2") (pintype "passive"))
      (node (ref "FB14") (pin "1") (pinfunction "1_1") (pintype "passive"))
      (node (ref "U23") (pin "3") (pinfunction "OUT_3") (pintype "output"))
    )
    (net (code "25") (name "Net-(U24-OUT)") (class "Default")
      (node (ref "C123") (pin "2") (pinfunction "2_2") (pintype "passive"))
      (node (ref "FB15") (pin "1") (pinfunction "1_1") (pintype "passive"))
      (node (ref "U24") (pin "1") (pinfunction "OUT_1") (pintype "power_in"))
    )
    (net (code "26") (name "unconnected-(T3-Pad5)") (class "Default")
      (node (ref "T3") (pin "5") (pinfunction "5_5") (pintype "passive"))
    )
    (net (code "27") (name "unconnected-(U17-DNC-Pad7)") (class "Default")
      (node (ref "U17") (pin "7") (pinfunction "DNC_7") (pintype "passive"))
    )
    (net (code "28") (name "unconnected-(U23-NC-Pad4)") (class "Default")
      (node (ref "U23") (pin "4") (pinfunction "NC_4") (pintype "power_in"))
    )
    (net (code "29") (name "unconnected-(U23-NC-Pad5)") (class "Default")
      (node (ref "U23") (pin "5") (pinfunction "NC_5") (pintype "power_in"))
    )
  )
)
